# ESPDHTNode.net
KiCad netlist of a schematic drawn in EAGLE
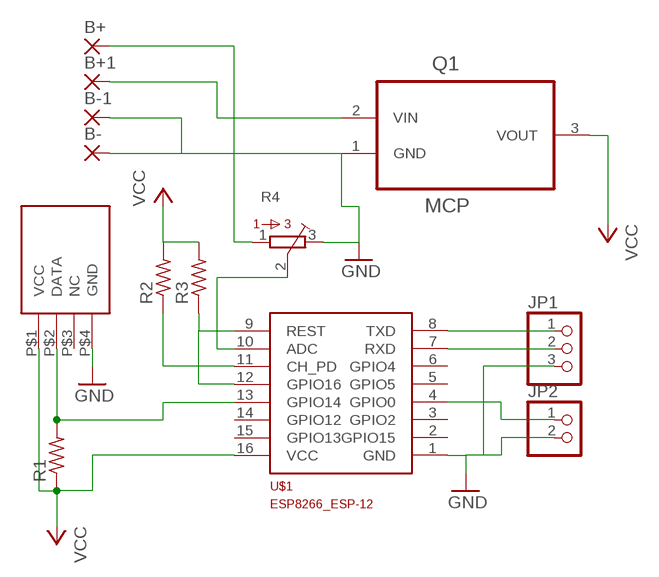
[diagram p0: schematic, sheet 1]

(export (version "E")
  (design (tool "Eeschema 10.0.6"))
  (components
    (comp (ref "B+")
      (value "WIREPAD2,54/0,8")
      (footprint "eagle-import:2,54_0,8")
      (libsource (lib "eagle-import") (part "WIREPAD2,54/0,8"))
    )
    (comp (ref "B+1")
      (value "WIREPAD2,54/0,8")
      (footprint "eagle-import:2,54_0,8")
      (libsource (lib "eagle-import") (part "WIREPAD2,54/0,8"))
    )
    (comp (ref "B-")
      (value "WIREPAD2,54/0,8")
      (footprint "eagle-import:2,54_0,8")
      (libsource (lib "eagle-import") (part "WIREPAD2,54/0,8"))
    )
    (comp (ref "B-1")
      (value "WIREPAD2,54/0,8")
      (footprint "eagle-import:2,54_0,8")
      (libsource (lib "eagle-import") (part "WIREPAD2,54/0,8"))
    )
    (comp (ref "JP1")
      (value "PINHD-1X3")
      (footprint "eagle-import:1X03")
      (libsource (lib "eagle-import") (part "PINHD-1X3"))
    )
    (comp (ref "JP2")
      (value "PINHD-1X2")
      (footprint "eagle-import:1X02")
      (libsource (lib "eagle-import") (part "PINHD-1X2"))
    )
    (comp (ref "Q1")
      (value "MCP")
      (footprint "eagle-import:TO127P254X533-3")
      (fields (field (name "MPN") "MCP1702-3302E/TO"))
      (libsource (lib "eagle-import") (part "MCP1702-3302E/TO"))
    )
    (comp (ref "R1")
      (value "R-US_0207/10")
      (footprint "eagle-import:0207_10")
      (libsource (lib "eagle-import") (part "R-US_0207/10"))
    )
    (comp (ref "R2")
      (value "R-US_0207/10")
      (footprint "eagle-import:0207_10")
      (libsource (lib "eagle-import") (part "R-US_0207/10"))
    )
    (comp (ref "R3")
      (value "R-US_0207/10")
      (footprint "eagle-import:0207_10")
      (libsource (lib "eagle-import") (part "R-US_0207/10"))
    )
    (comp (ref "R4")
      (value "3362P")
      (footprint "eagle-import:3362P")
      (libsource (lib "eagle-import") (part "3362P"))
    )
    (comp (ref "U$1")
      (value "ESP8266_ESP-12")
      (footprint "eagle-import:ESP8266-ESP12")
      (libsource (lib "eagle-import") (part "ESP8266_ESP-12"))
    )
    (comp (ref "U$2")
      (value "DHTDHT11")
      (footprint "eagle-import:DHT")
      (libsource (lib "eagle-import") (part "DHTDHT11"))
    )
  )
  (nets
    (net (code "1") (name "GND") (class "Default")
      (node (ref "B-") (pin "1") (pinfunction "P_1") (pintype "passive"))
      (node (ref "B-1") (pin "1") (pinfunction "P_1") (pintype "passive"))
      (node (ref "JP1") (pin "3") (pinfunction "3_3") (pintype "passive"))
      (node (ref "JP2") (pin "2") (pinfunction "2_2") (pintype "passive"))
      (node (ref "Q1") (pin "1") (pinfunction "GND_1") (pintype "passive"))
      (node (ref "R4") (pin "3") (pinfunction "3_3") (pintype "passive"))
      (node (ref "U$1") (pin "1") (pinfunction "GND_1") (pintype "bidirectional"))
      (node (ref "U$2") (pin "P$4") (pinfunction "GND_P$4") (pintype "bidirectional"))
    )
    (net (code "2") (name "Net-(B+-P)") (class "Default")
      (node (ref "B+") (pin "1") (pinfunction "P_1") (pintype "passive"))
      (node (ref "B+1") (pin "1") (pinfunction "P_1") (pintype "passive"))
      (node (ref "Q1") (pin "2") (pinfunction "VIN_2") (pintype "input"))
      (node (ref "R4") (pin "1") (pinfunction "1_1") (pintype "passive"))
    )
    (net (code "3") (name "Net-(U$1-ADC)") (class "Default")
      (node (ref "R4") (pin "2") (pinfunction "2_2") (pintype "passive"))
      (node (ref "U$1") (pin "10") (pinfunction "ADC_10") (pintype "bidirectional"))
    )
    (net (code "4") (name "Net-(U$1-CH_PD)") (class "Default")
      (node (ref "R2") (pin "1") (pinfunction "1_1") (pintype "passive"))
      (node (ref "U$1") (pin "11") (pinfunction "CH_PD_11") (pintype "bidirectional"))
    )
    (net (code "5") (name "Net-(U$1-GPIO0)") (class "Default")
      (node (ref "JP2") (pin "1") (pinfunction "1_1") (pintype "passive"))
      (node (ref "U$1") (pin "4") (pinfunction "GPIO0_4") (pintype "bidirectional"))
    )
    (net (code "6") (name "Net-(U$1-GPIO14)") (class "Default")
      (node (ref "R1") (pin "2") (pinfunction "2_2") (pintype "passive"))
      (node (ref "U$1") (pin "13") (pinfunction "GPIO14_13") (pintype "bidirectional"))
      (node (ref "U$2") (pin "P$2") (pinfunction "DATA_P$2") (pintype "bidirectional"))
    )
    (net (code "7") (name "Net-(U$1-GPIO16)") (class "Default")
      (node (ref "R3") (pin "1") (pinfunction "1_1") (pintype "passive"))
      (node (ref "U$1") (pin "12") (pinfunction "GPIO16_12") (pintype "bidirectional"))
      (node (ref "U$1") (pin "9") (pinfunction "REST_9") (pintype "bidirectional"))
    )
    (net (code "8") (name "Net-(U$1-RXD)") (class "Default")
      (node (ref "JP1") (pin "2") (pinfunction "2_2") (pintype "passive"))
      (node (ref "U$1") (pin "7") (pinfunction "RXD_7") (pintype "bidirectional"))
    )
    (net (code "9") (name "Net-(U$1-TXD)") (class "Default")
      (node (ref "JP1") (pin "1") (pinfunction "1_1") (pintype "passive"))
      (node (ref "U$1") (pin "8") (pinfunction "TXD_8") (pintype "bidirectional"))
    )
    (net (code "10") (name "VCC") (class "Default")
      (node (ref "Q1") (pin "3") (pinfunction "VOUT_3") (pintype "output"))
      (node (ref "R1") (pin "1") (pinfunction "1_1") (pintype "passive"))
      (node (ref "R2") (pin "2") (pinfunction "2_2") (pintype "passive"))
      (node (ref "R3") (pin "2") (pinfunction "2_2") (pintype "passive"))
      (node (ref "U$1") (pin "16") (pinfunction "VCC_16") (pintype "bidirectional"))
      (node (ref "U$2") (pin "P$1") (pinfunction "VCC_P$1") (pintype "bidirectional"))
    )
    (net (code "11") (name "unconnected-(U$1-GPIO2-Pad3)") (class "Default")
      (node (ref "U$1") (pin "3") (pinfunction "GPIO2_3") (pintype "bidirectional"))
    )
    (net (code "12") (name "unconnected-(U$1-GPIO4-Pad6)") (class "Default")
      (node (ref "U$1") (pin "6") (pinfunction "GPIO4_6") (pintype "bidirectional"))
    )
    (net (code "13") (name "unconnected-(U$1-GPIO5-Pad5)") (class "Default")
      (node (ref "U$1") (pin "5") (pinfunction "GPIO5_5") (pintype "bidirectional"))
    )
    (net (code "14") (name "unconnected-(U$1-GPIO12-Pad14)") (class "Default")
      (node (ref "U$1") (pin "14") (pinfunction "GPIO12_14") (pintype "bidirectional"))
    )
    (net (code "15") (name "unconnected-(U$1-GPIO13-Pad15)") (class "Default")
      (node (ref "U$1") (pin "15") (pinfunction "GPIO13_15") (pintype "bidirectional"))
    )
    (net (code "16") (name "unconnected-(U$1-GPIO15-Pad2)") (class "Default")
      (node (ref "U$1") (pin "2") (pinfunction "GPIO15_2") (pintype "bidirectional"))
    )
    (net (code "17") (name "unconnected-(U$2-NC-PadP$3)") (class "Default")
      (node (ref "U$2") (pin "P$3") (pinfunction "NC_P$3") (pintype "bidirectional"))
    )
  )
)
